# s-isp.net
KiCad netlist of a schematic drawn in EAGLE
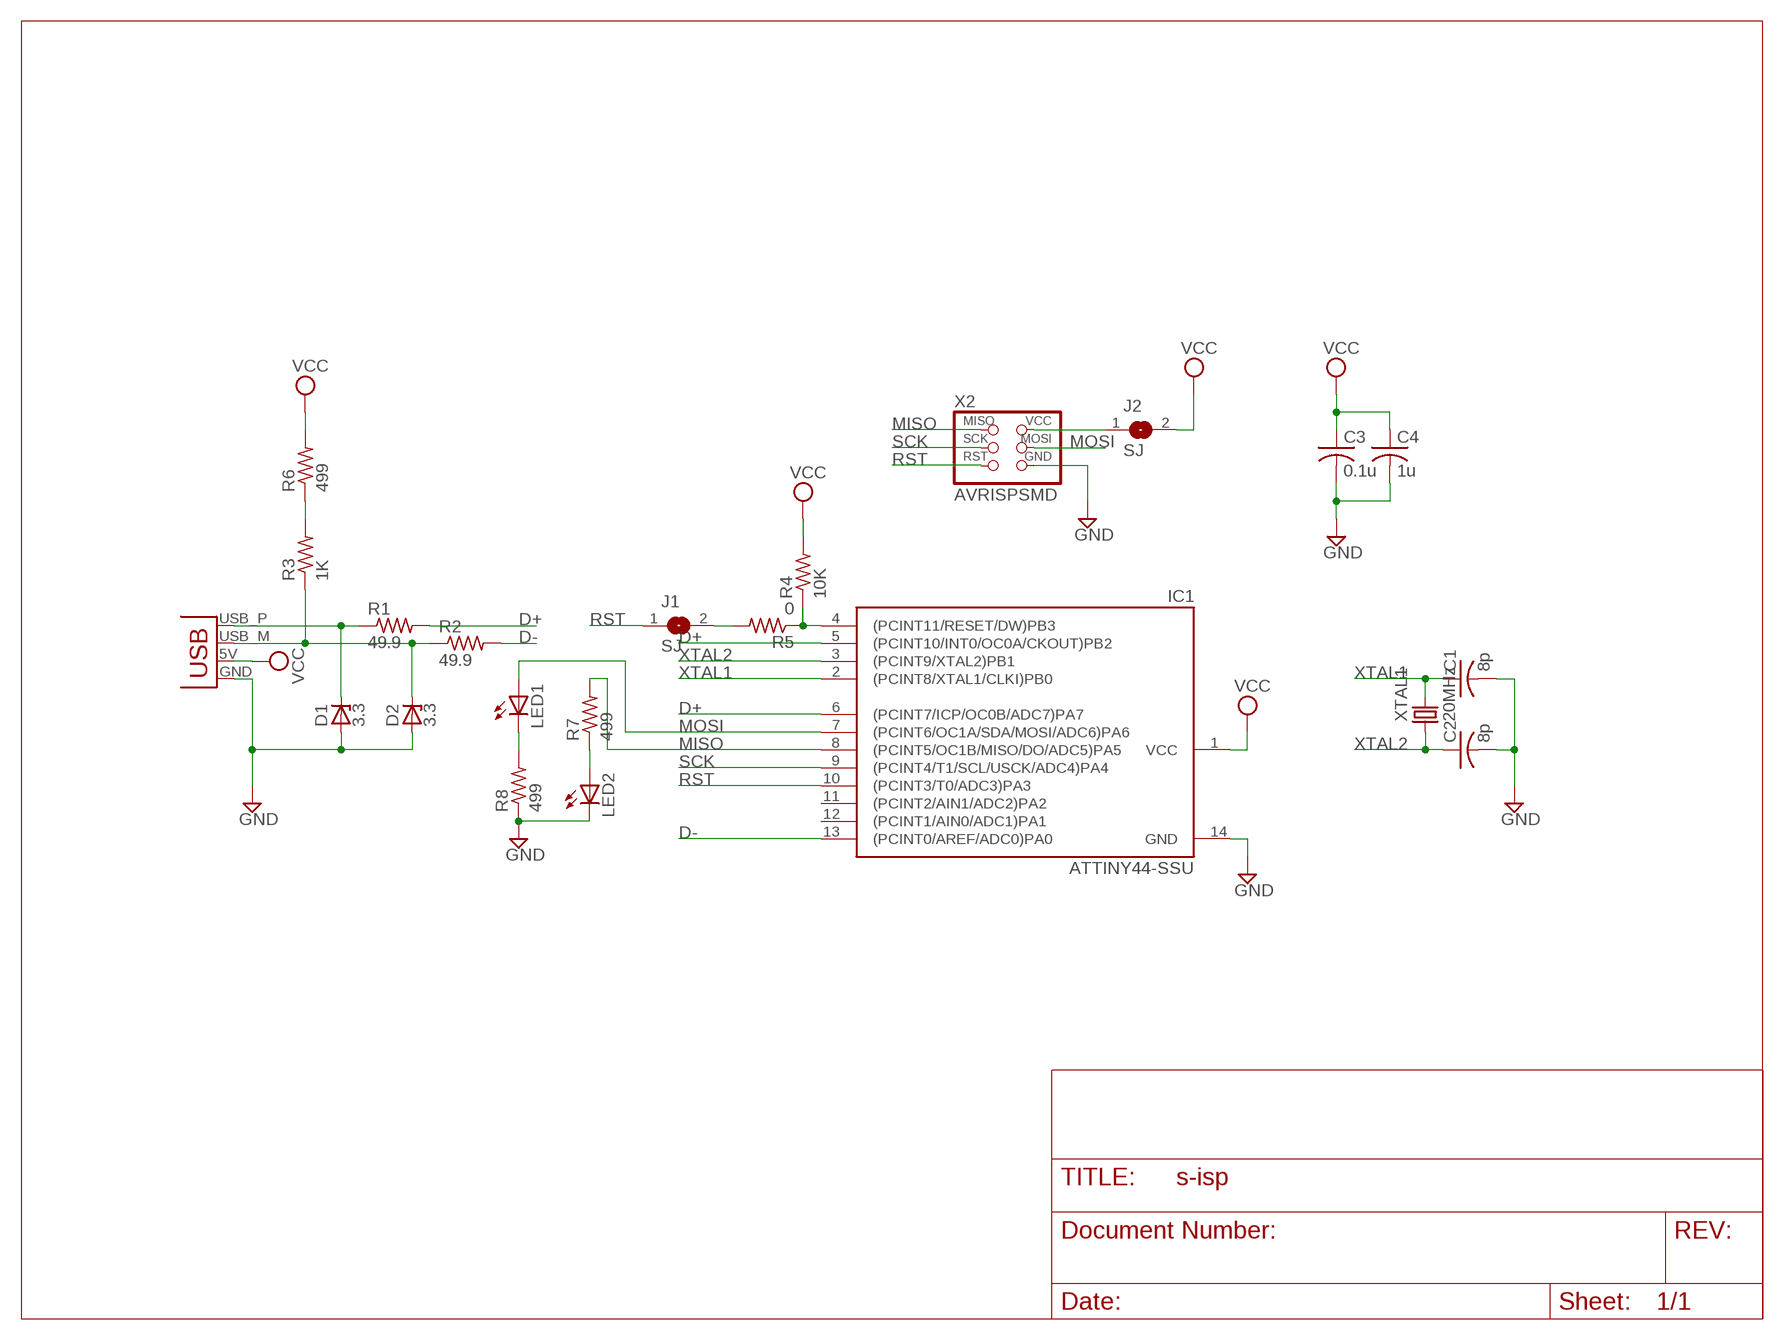
[diagram p0: schematic, sheet 1]

(export (version "E")
  (design (tool "Eeschema 10.0.6"))
  (components
    (comp (ref "C1")
      (value "8p")
      (footprint "eagle-import:C1206")
      (libsource (lib "eagle-import") (part "C-USC1206"))
    )
    (comp (ref "C2")
      (value "8p")
      (footprint "eagle-import:C1206")
      (libsource (lib "eagle-import") (part "C-USC1206"))
    )
    (comp (ref "C3")
      (value "0.1u")
      (footprint "eagle-import:C1206")
      (libsource (lib "eagle-import") (part "C-USC1206"))
    )
    (comp (ref "C4")
      (value "1u")
      (footprint "eagle-import:C1206")
      (libsource (lib "eagle-import") (part "C-USC1206"))
    )
    (comp (ref "D1")
      (value "3.3")
      (footprint "eagle-import:SOD123")
      (libsource (lib "eagle-import") (part "ZENER_DIODESOD123"))
    )
    (comp (ref "D2")
      (value "3.3")
      (footprint "eagle-import:SOD123")
      (libsource (lib "eagle-import") (part "ZENER_DIODESOD123"))
    )
    (comp (ref "IC1")
      (value "ATTINY44-SSU")
      (footprint "eagle-import:SOIC14")
      (libsource (lib "eagle-import") (part "ATTINY44-SSU"))
    )
    (comp (ref "J1")
      (value "SJ")
      (footprint "eagle-import:SJFAB")
      (libsource (lib "eagle-import") (part "SOLDER_JUMPER"))
    )
    (comp (ref "J2")
      (value "SJ")
      (footprint "eagle-import:SJFAB")
      (libsource (lib "eagle-import") (part "SOLDER_JUMPER"))
    )
    (comp (ref "LED1")
      (value "LEDSMT1206")
      (footprint "eagle-import:1206")
      (libsource (lib "eagle-import") (part "LEDSMT1206"))
    )
    (comp (ref "LED2")
      (value "LEDSMT1206")
      (footprint "eagle-import:1206")
      (libsource (lib "eagle-import") (part "LEDSMT1206"))
    )
    (comp (ref "R1")
      (value "49.9")
      (footprint "eagle-import:R1206")
      (libsource (lib "eagle-import") (part "R-US_R1206"))
    )
    (comp (ref "R2")
      (value "49.9")
      (footprint "eagle-import:R1206")
      (libsource (lib "eagle-import") (part "R-US_R1206"))
    )
    (comp (ref "R3")
      (value "1K")
      (footprint "eagle-import:R1206")
      (libsource (lib "eagle-import") (part "R-US_R1206"))
    )
    (comp (ref "R4")
      (value "10K")
      (footprint "eagle-import:R1206")
      (libsource (lib "eagle-import") (part "R-US_R1206"))
    )
    (comp (ref "R5")
      (value "0")
      (footprint "eagle-import:R1206")
      (libsource (lib "eagle-import") (part "R-US_R1206"))
    )
    (comp (ref "R6")
      (value "499")
      (footprint "eagle-import:R1206")
      (libsource (lib "eagle-import") (part "R-US_R1206"))
    )
    (comp (ref "R7")
      (value "499")
      (footprint "eagle-import:R1206")
      (libsource (lib "eagle-import") (part "R-US_R1206"))
    )
    (comp (ref "R8")
      (value "499")
      (footprint "eagle-import:R1206")
      (libsource (lib "eagle-import") (part "R-US_R1206"))
    )
    (comp (ref "X1")
      (value "USBPCB")
      (footprint "eagle-import:USB-A-PCB")
      (libsource (lib "eagle-import") (part "USBPCB"))
    )
    (comp (ref "X2")
      (value "AVRISPSMD")
      (footprint "eagle-import:2X03SMD")
      (libsource (lib "eagle-import") (part "AVRISPSMD"))
    )
    (comp (ref "XTAL1")
      (value "20MHz")
      (footprint "eagle-import:2-SMD-5X3MM")
      (libsource (lib "eagle-import") (part "CRYSTAL"))
    )
  )
  (nets
    (net (code "1") (name "/D+") (class "Default")
      (node (ref "IC1") (pin "5") (pinfunction "(PCINT10/INT0/OC0A/CKOUT)PB2_5") (pintype "bidirectional"))
      (node (ref "IC1") (pin "6") (pinfunction "(PCINT7/ICP/OC0B/ADC7)PA7_6") (pintype "bidirectional"))
      (node (ref "R1") (pin "2") (pinfunction "2_2") (pintype "passive"))
    )
    (net (code "2") (name "/D-") (class "Default")
      (node (ref "IC1") (pin "13") (pinfunction "(PCINT0/AREF/ADC0)PA0_13") (pintype "bidirectional"))
      (node (ref "R2") (pin "2") (pinfunction "2_2") (pintype "passive"))
    )
    (net (code "3") (name "/MISO") (class "Default")
      (node (ref "IC1") (pin "8") (pinfunction "(PCINT5/OC1B/MISO/DO/ADC5)PA5_8") (pintype "bidirectional"))
      (node (ref "R7") (pin "2") (pinfunction "2_2") (pintype "passive"))
      (node (ref "X2") (pin "1") (pinfunction "MISO_1") (pintype "passive"))
    )
    (net (code "4") (name "/MOSI") (class "Default")
      (node (ref "IC1") (pin "7") (pinfunction "(PCINT6/OC1A/SDA/MOSI/ADC6)PA6_7") (pintype "bidirectional"))
      (node (ref "LED1") (pin "A") (pinfunction "A_A") (pintype "passive"))
      (node (ref "X2") (pin "4") (pinfunction "MOSI_4") (pintype "passive"))
    )
    (net (code "5") (name "/RST") (class "Default")
      (node (ref "IC1") (pin "10") (pinfunction "(PCINT3/T0/ADC3)PA3_10") (pintype "bidirectional"))
      (node (ref "J1") (pin "1") (pinfunction "1_1") (pintype "passive"))
      (node (ref "X2") (pin "5") (pinfunction "RST_5") (pintype "passive"))
    )
    (net (code "6") (name "/SCK") (class "Default")
      (node (ref "IC1") (pin "9") (pinfunction "(PCINT4/T1/SCL/USCK/ADC4)PA4_9") (pintype "bidirectional"))
      (node (ref "X2") (pin "3") (pinfunction "SCK_3") (pintype "passive"))
    )
    (net (code "7") (name "/XTAL1") (class "Default")
      (node (ref "C1") (pin "1") (pinfunction "1_1") (pintype "passive"))
      (node (ref "IC1") (pin "2") (pinfunction "(PCINT8/XTAL1/CLKI)PB0_2") (pintype "bidirectional"))
      (node (ref "XTAL1") (pin "P$2") (pinfunction "2_P$2") (pintype "passive"))
    )
    (net (code "8") (name "/XTAL2") (class "Default")
      (node (ref "C2") (pin "1") (pinfunction "1_1") (pintype "passive"))
      (node (ref "IC1") (pin "3") (pinfunction "(PCINT9/XTAL2)PB1_3") (pintype "bidirectional"))
      (node (ref "XTAL1") (pin "P$1") (pinfunction "1_P$1") (pintype "passive"))
    )
    (net (code "9") (name "GND") (class "Default")
      (node (ref "C1") (pin "2") (pinfunction "2_2") (pintype "passive"))
      (node (ref "C2") (pin "2") (pinfunction "2_2") (pintype "passive"))
      (node (ref "C3") (pin "2") (pinfunction "2_2") (pintype "passive"))
      (node (ref "C4") (pin "2") (pinfunction "2_2") (pintype "passive"))
      (node (ref "D1") (pin "ANODE") (pinfunction "ANODE_ANODE") (pintype "passive"))
      (node (ref "D2") (pin "ANODE") (pinfunction "ANODE_ANODE") (pintype "passive"))
      (node (ref "IC1") (pin "14") (pinfunction "GND_14") (pintype "power_in"))
      (node (ref "LED2") (pin "C") (pinfunction "C_C") (pintype "passive"))
      (node (ref "R8") (pin "1") (pinfunction "1_1") (pintype "passive"))
      (node (ref "X1") (pin "GND") (pinfunction "GND_GND") (pintype "bidirectional"))
      (node (ref "X2") (pin "6") (pinfunction "GND_6") (pintype "passive"))
    )
    (net (code "10") (name "Net-(IC1-(PCINT11{slash}RESET{slash}DW)PB3)") (class "Default")
      (node (ref "IC1") (pin "4") (pinfunction "(PCINT11/RESET/DW)PB3_4") (pintype "bidirectional"))
      (node (ref "R4") (pin "1") (pinfunction "1_1") (pintype "passive"))
      (node (ref "R5") (pin "1") (pinfunction "1_1") (pintype "passive"))
    )
    (net (code "11") (name "Net-(J1-Pad2)") (class "Default")
      (node (ref "J1") (pin "2") (pinfunction "2_2") (pintype "passive"))
      (node (ref "R5") (pin "2") (pinfunction "2_2") (pintype "passive"))
    )
    (net (code "12") (name "Net-(LED1-PadC)") (class "Default")
      (node (ref "LED1") (pin "C") (pinfunction "C_C") (pintype "passive"))
      (node (ref "R8") (pin "2") (pinfunction "2_2") (pintype "passive"))
    )
    (net (code "13") (name "Net-(LED2-PadA)") (class "Default")
      (node (ref "LED2") (pin "A") (pinfunction "A_A") (pintype "passive"))
      (node (ref "R7") (pin "1") (pinfunction "1_1") (pintype "passive"))
    )
    (net (code "14") (name "Net-(R3-Pad2)") (class "Default")
      (node (ref "R3") (pin "2") (pinfunction "2_2") (pintype "passive"))
      (node (ref "R6") (pin "1") (pinfunction "1_1") (pintype "passive"))
    )
    (net (code "15") (name "Net-(X1-D+)") (class "Default")
      (node (ref "D1") (pin "CATHODE") (pinfunction "CATHODE_CATHODE") (pintype "passive"))
      (node (ref "R1") (pin "1") (pinfunction "1_1") (pintype "passive"))
      (node (ref "X1") (pin "USB_P") (pinfunction "D+_USB_P") (pintype "bidirectional"))
    )
    (net (code "16") (name "Net-(X1-D-)") (class "Default")
      (node (ref "D2") (pin "CATHODE") (pinfunction "CATHODE_CATHODE") (pintype "passive"))
      (node (ref "R2") (pin "1") (pinfunction "1_1") (pintype "passive"))
      (node (ref "R3") (pin "1") (pinfunction "1_1") (pintype "passive"))
      (node (ref "X1") (pin "USB_M") (pinfunction "D-_USB_M") (pintype "bidirectional"))
    )
    (net (code "17") (name "Net-(X2-VCC)") (class "Default")
      (node (ref "J2") (pin "1") (pinfunction "1_1") (pintype "passive"))
      (node (ref "X2") (pin "2") (pinfunction "VCC_2") (pintype "passive"))
    )
    (net (code "18") (name "VCC") (class "Default")
      (node (ref "C3") (pin "1") (pinfunction "1_1") (pintype "passive"))
      (node (ref "C4") (pin "1") (pinfunction "1_1") (pintype "passive"))
      (node (ref "IC1") (pin "1") (pinfunction "VCC_1") (pintype "power_in"))
      (node (ref "J2") (pin "2") (pinfunction "2_2") (pintype "passive"))
      (node (ref "R4") (pin "2") (pinfunction "2_2") (pintype "passive"))
      (node (ref "R6") (pin "2") (pinfunction "2_2") (pintype "passive"))
      (node (ref "X1") (pin "5V") (pinfunction "VBUS_5V") (pintype "bidirectional"))
    )
    (net (code "19") (name "unconnected-(IC1-(PCINT1{slash}AIN0{slash}ADC1)PA1-Pad12)") (class "Default")
      (node (ref "IC1") (pin "12") (pinfunction "(PCINT1/AIN0/ADC1)PA1_12") (pintype "bidirectional"))
    )
    (net (code "20") (name "unconnected-(IC1-(PCINT2{slash}AIN1{slash}ADC2)PA2-Pad11)") (class "Default")
      (node (ref "IC1") (pin "11") (pinfunction "(PCINT2/AIN1/ADC2)PA2_11") (pintype "bidirectional"))
    )
  )
)
